# pyControl_devboard_1_2.net
KiCad netlist of a schematic drawn in EAGLE
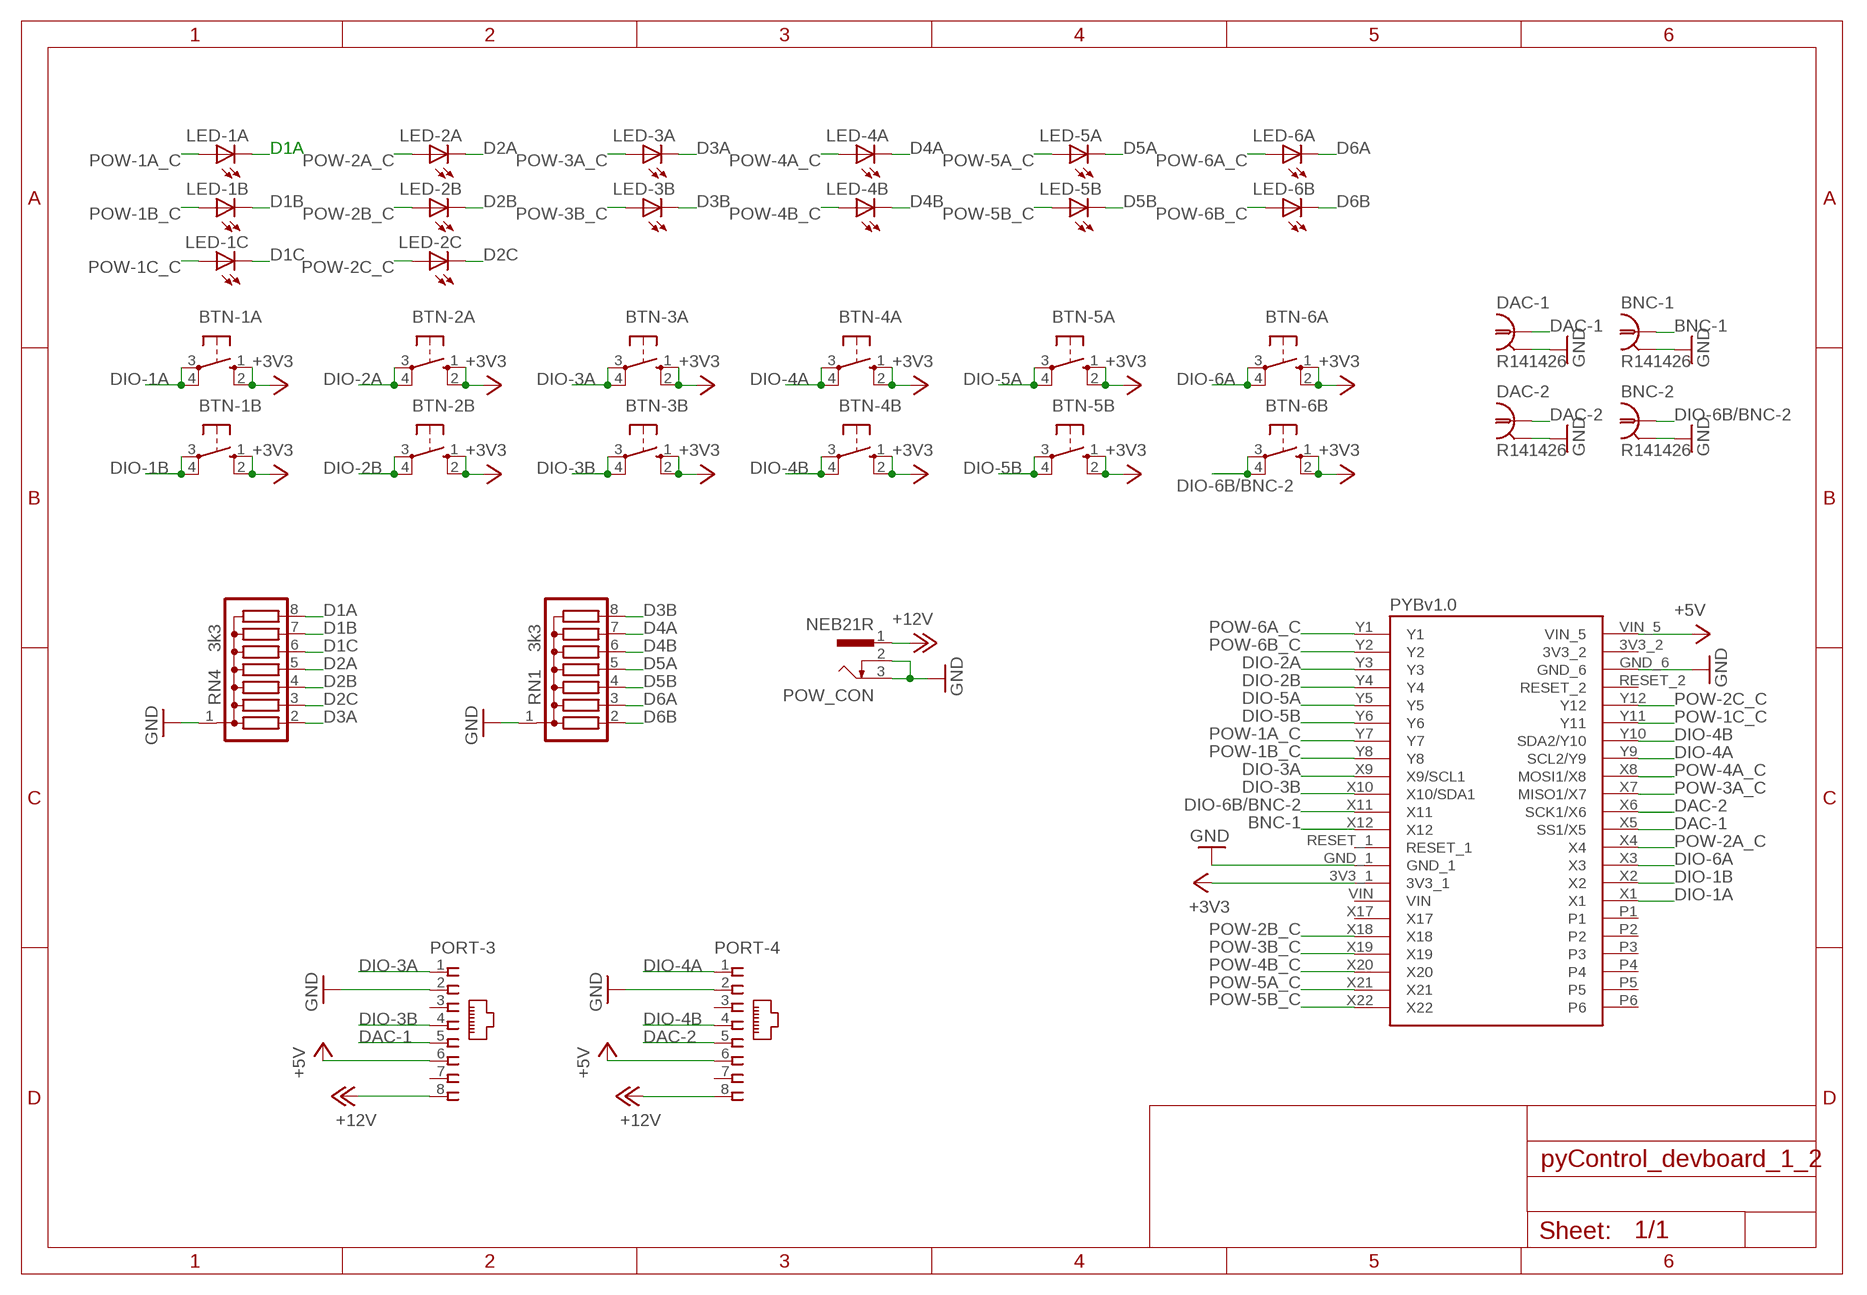
[diagram p0: schematic, sheet 1]

(export (version "E")
  (design (tool "Eeschema 10.0.6"))
  (components
    (comp (ref "BNC-1")
      (value "R141426")
      (footprint "eagle-import:R141426")
      (fields (field (name "MF") "FARNELL") (field (name "MPN") "R141426161"))
      (libsource (lib "eagle-import") (part "R141426"))
    )
    (comp (ref "BNC-2")
      (value "R141426")
      (footprint "eagle-import:R141426")
      (fields (field (name "MF") "FARNELL") (field (name "MPN") "R141426161"))
      (libsource (lib "eagle-import") (part "R141426"))
    )
    (comp (ref "BTN-1A")
      (value "40-XX")
      (footprint "eagle-import:B3F-40XX")
      (fields
        (field (name "MF") "OMRON COMPONENTS USA")
        (field (name "MPN") "B3F-4000")
        (field (name "MF_1") "OMRON COMPONENTS USA")
        (field (name "MPN_1") "B3F-4000")
        (field (name "OC_FARNELL") "176434")
        (field (name "OC_NEWARK") "36K3105")
      )
      (libsource (lib "eagle-import") (part "40-XX"))
    )
    (comp (ref "BTN-1B")
      (value "40-XX")
      (footprint "eagle-import:B3F-40XX")
      (fields
        (field (name "MF") "OMRON COMPONENTS USA")
        (field (name "MPN") "B3F-4000")
        (field (name "MF_1") "OMRON COMPONENTS USA")
        (field (name "MPN_1") "B3F-4000")
        (field (name "OC_FARNELL") "176434")
        (field (name "OC_NEWARK") "36K3105")
      )
      (libsource (lib "eagle-import") (part "40-XX"))
    )
    (comp (ref "BTN-2A")
      (value "40-XX")
      (footprint "eagle-import:B3F-40XX")
      (fields
        (field (name "MF") "OMRON COMPONENTS USA")
        (field (name "MPN") "B3F-4000")
        (field (name "MF_1") "OMRON COMPONENTS USA")
        (field (name "MPN_1") "B3F-4000")
        (field (name "OC_FARNELL") "176434")
        (field (name "OC_NEWARK") "36K3105")
      )
      (libsource (lib "eagle-import") (part "40-XX"))
    )
    (comp (ref "BTN-2B")
      (value "40-XX")
      (footprint "eagle-import:B3F-40XX")
      (fields
        (field (name "MF") "OMRON COMPONENTS USA")
        (field (name "MPN") "B3F-4000")
        (field (name "MF_1") "OMRON COMPONENTS USA")
        (field (name "MPN_1") "B3F-4000")
        (field (name "OC_FARNELL") "176434")
        (field (name "OC_NEWARK") "36K3105")
      )
      (libsource (lib "eagle-import") (part "40-XX"))
    )
    (comp (ref "BTN-3A")
      (value "40-XX")
      (footprint "eagle-import:B3F-40XX")
      (fields
        (field (name "MF") "OMRON COMPONENTS USA")
        (field (name "MPN") "B3F-4000")
        (field (name "MF_1") "OMRON COMPONENTS USA")
        (field (name "MPN_1") "B3F-4000")
        (field (name "OC_FARNELL") "176434")
        (field (name "OC_NEWARK") "36K3105")
      )
      (libsource (lib "eagle-import") (part "40-XX"))
    )
    (comp (ref "BTN-3B")
      (value "40-XX")
      (footprint "eagle-import:B3F-40XX")
      (fields
        (field (name "MF") "OMRON COMPONENTS USA")
        (field (name "MPN") "B3F-4000")
        (field (name "MF_1") "OMRON COMPONENTS USA")
        (field (name "MPN_1") "B3F-4000")
        (field (name "OC_FARNELL") "176434")
        (field (name "OC_NEWARK") "36K3105")
      )
      (libsource (lib "eagle-import") (part "40-XX"))
    )
    (comp (ref "BTN-4A")
      (value "40-XX")
      (footprint "eagle-import:B3F-40XX")
      (fields
        (field (name "MF") "OMRON COMPONENTS USA")
        (field (name "MPN") "B3F-4000")
        (field (name "MF_1") "OMRON COMPONENTS USA")
        (field (name "MPN_1") "B3F-4000")
        (field (name "OC_FARNELL") "176434")
        (field (name "OC_NEWARK") "36K3105")
      )
      (libsource (lib "eagle-import") (part "40-XX"))
    )
    (comp (ref "BTN-4B")
      (value "40-XX")
      (footprint "eagle-import:B3F-40XX")
      (fields
        (field (name "MF") "OMRON COMPONENTS USA")
        (field (name "MPN") "B3F-4000")
        (field (name "MF_1") "OMRON COMPONENTS USA")
        (field (name "MPN_1") "B3F-4000")
        (field (name "OC_FARNELL") "176434")
        (field (name "OC_NEWARK") "36K3105")
      )
      (libsource (lib "eagle-import") (part "40-XX"))
    )
    (comp (ref "BTN-5A")
      (value "40-XX")
      (footprint "eagle-import:B3F-40XX")
      (fields
        (field (name "MF") "OMRON COMPONENTS USA")
        (field (name "MPN") "B3F-4000")
        (field (name "MF_1") "OMRON COMPONENTS USA")
        (field (name "MPN_1") "B3F-4000")
        (field (name "OC_FARNELL") "176434")
        (field (name "OC_NEWARK") "36K3105")
      )
      (libsource (lib "eagle-import") (part "40-XX"))
    )
    (comp (ref "BTN-5B")
      (value "40-XX")
      (footprint "eagle-import:B3F-40XX")
      (fields
        (field (name "MF") "OMRON COMPONENTS USA")
        (field (name "MPN") "B3F-4000")
        (field (name "MF_1") "OMRON COMPONENTS USA")
        (field (name "MPN_1") "B3F-4000")
        (field (name "OC_FARNELL") "176434")
        (field (name "OC_NEWARK") "36K3105")
      )
      (libsource (lib "eagle-import") (part "40-XX"))
    )
    (comp (ref "BTN-6A")
      (value "40-XX")
      (footprint "eagle-import:B3F-40XX")
      (fields
        (field (name "MF") "OMRON COMPONENTS USA")
        (field (name "MPN") "B3F-4000")
        (field (name "MF_1") "OMRON COMPONENTS USA")
        (field (name "MPN_1") "B3F-4000")
        (field (name "OC_FARNELL") "176434")
        (field (name "OC_NEWARK") "36K3105")
      )
      (libsource (lib "eagle-import") (part "40-XX"))
    )
    (comp (ref "BTN-6B")
      (value "40-XX")
      (footprint "eagle-import:B3F-40XX")
      (fields
        (field (name "MF") "OMRON COMPONENTS USA")
        (field (name "MPN") "B3F-4000")
        (field (name "MF_1") "OMRON COMPONENTS USA")
        (field (name "MPN_1") "B3F-4000")
        (field (name "OC_FARNELL") "176434")
        (field (name "OC_NEWARK") "36K3105")
      )
      (libsource (lib "eagle-import") (part "40-XX"))
    )
    (comp (ref "DAC-1")
      (value "R141426")
      (footprint "eagle-import:R141426")
      (fields (field (name "MF") "FARNELL") (field (name "MPN") "R141426161"))
      (libsource (lib "eagle-import") (part "R141426"))
    )
    (comp (ref "DAC-2")
      (value "R141426")
      (footprint "eagle-import:R141426")
      (fields (field (name "MF") "FARNELL") (field (name "MPN") "R141426161"))
      (libsource (lib "eagle-import") (part "R141426"))
    )
    (comp (ref "LED-1A")
      (value "LED3MM")
      (footprint "eagle-import:LED3MM")
      (libsource (lib "eagle-import") (part "LED3MM"))
    )
    (comp (ref "LED-1B")
      (value "LED3MM")
      (footprint "eagle-import:LED3MM")
      (libsource (lib "eagle-import") (part "LED3MM"))
    )
    (comp (ref "LED-1C")
      (value "LED3MM")
      (footprint "eagle-import:LED3MM")
      (libsource (lib "eagle-import") (part "LED3MM"))
    )
    (comp (ref "LED-2A")
      (value "LED3MM")
      (footprint "eagle-import:LED3MM")
      (libsource (lib "eagle-import") (part "LED3MM"))
    )
    (comp (ref "LED-2B")
      (value "LED3MM")
      (footprint "eagle-import:LED3MM")
      (libsource (lib "eagle-import") (part "LED3MM"))
    )
    (comp (ref "LED-2C")
      (value "LED3MM")
      (footprint "eagle-import:LED3MM")
      (libsource (lib "eagle-import") (part "LED3MM"))
    )
    (comp (ref "LED-3A")
      (value "LED3MM")
      (footprint "eagle-import:LED3MM")
      (libsource (lib "eagle-import") (part "LED3MM"))
    )
    (comp (ref "LED-3B")
      (value "LED3MM")
      (footprint "eagle-import:LED3MM")
      (libsource (lib "eagle-import") (part "LED3MM"))
    )
    (comp (ref "LED-4A")
      (value "LED3MM")
      (footprint "eagle-import:LED3MM")
      (libsource (lib "eagle-import") (part "LED3MM"))
    )
    (comp (ref "LED-4B")
      (value "LED3MM")
      (footprint "eagle-import:LED3MM")
      (libsource (lib "eagle-import") (part "LED3MM"))
    )
    (comp (ref "LED-5A")
      (value "LED3MM")
      (footprint "eagle-import:LED3MM")
      (libsource (lib "eagle-import") (part "LED3MM"))
    )
    (comp (ref "LED-5B")
      (value "LED3MM")
      (footprint "eagle-import:LED3MM")
      (libsource (lib "eagle-import") (part "LED3MM"))
    )
    (comp (ref "LED-6A")
      (value "LED3MM")
      (footprint "eagle-import:LED3MM")
      (libsource (lib "eagle-import") (part "LED3MM"))
    )
    (comp (ref "LED-6B")
      (value "LED3MM")
      (footprint "eagle-import:LED3MM")
      (libsource (lib "eagle-import") (part "LED3MM"))
    )
    (comp (ref "PORT-3")
      (value "RJ45VERTICAL")
      (footprint "eagle-import:RJ45-NO-SHIELD-VERTICAL")
      (libsource (lib "eagle-import") (part "RJ45VERTICAL"))
    )
    (comp (ref "PORT-4")
      (value "RJ45VERTICAL")
      (footprint "eagle-import:RJ45-NO-SHIELD-VERTICAL")
      (libsource (lib "eagle-import") (part "RJ45VERTICAL"))
    )
    (comp (ref "POW_CON")
      (value "NEB21R")
      (footprint "eagle-import:NEB21R")
      (fields (field (name "MPN") "NEB 21 R"))
      (libsource (lib "eagle-import") (part "NEB21R"))
    )
    (comp (ref "PYBOARD")
      (value "PYBOARD-REDUCED-2")
      (footprint "eagle-import:PYBOARD-REDUCED-2")
      (libsource (lib "eagle-import") (part "PYBOARD-REDUCED-2"))
    )
    (comp (ref "RN1")
      (value "3k3")
      (footprint "eagle-import:SIL8")
      (libsource (lib "eagle-import") (part "G07R"))
    )
    (comp (ref "RN4")
      (value "3k3")
      (footprint "eagle-import:SIL8")
      (libsource (lib "eagle-import") (part "G07R"))
    )
  )
  (nets
    (net (code "1") (name "+3V3") (class "Default")
      (node (ref "BTN-1A") (pin "1") (pinfunction "S_1") (pintype "passive"))
      (node (ref "BTN-1A") (pin "2") (pinfunction "S1_2") (pintype "passive"))
      (node (ref "BTN-1B") (pin "1") (pinfunction "S_1") (pintype "passive"))
      (node (ref "BTN-1B") (pin "2") (pinfunction "S1_2") (pintype "passive"))
      (node (ref "BTN-2A") (pin "1") (pinfunction "S_1") (pintype "passive"))
      (node (ref "BTN-2A") (pin "2") (pinfunction "S1_2") (pintype "passive"))
      (node (ref "BTN-2B") (pin "1") (pinfunction "S_1") (pintype "passive"))
      (node (ref "BTN-2B") (pin "2") (pinfunction "S1_2") (pintype "passive"))
      (node (ref "BTN-3A") (pin "1") (pinfunction "S_1") (pintype "passive"))
      (node (ref "BTN-3A") (pin "2") (pinfunction "S1_2") (pintype "passive"))
      (node (ref "BTN-3B") (pin "1") (pinfunction "S_1") (pintype "passive"))
      (node (ref "BTN-3B") (pin "2") (pinfunction "S1_2") (pintype "passive"))
      (node (ref "BTN-4A") (pin "1") (pinfunction "S_1") (pintype "passive"))
      (node (ref "BTN-4A") (pin "2") (pinfunction "S1_2") (pintype "passive"))
      (node (ref "BTN-4B") (pin "1") (pinfunction "S_1") (pintype "passive"))
      (node (ref "BTN-4B") (pin "2") (pinfunction "S1_2") (pintype "passive"))
      (node (ref "BTN-5A") (pin "1") (pinfunction "S_1") (pintype "passive"))
      (node (ref "BTN-5A") (pin "2") (pinfunction "S1_2") (pintype "passive"))
      (node (ref "BTN-5B") (pin "1") (pinfunction "S_1") (pintype "passive"))
      (node (ref "BTN-5B") (pin "2") (pinfunction "S1_2") (pintype "passive"))
      (node (ref "BTN-6A") (pin "1") (pinfunction "S_1") (pintype "passive"))
      (node (ref "BTN-6A") (pin "2") (pinfunction "S1_2") (pintype "passive"))
      (node (ref "BTN-6B") (pin "1") (pinfunction "S_1") (pintype "passive"))
      (node (ref "BTN-6B") (pin "2") (pinfunction "S1_2") (pintype "passive"))
      (node (ref "PYBOARD") (pin "3V3_1") (pinfunction "3V3_1_3V3_1") (pintype "bidirectional"))
    )
    (net (code "2") (name "+5V") (class "Default")
      (node (ref "PORT-3") (pin "6") (pinfunction "6_6") (pintype "passive"))
      (node (ref "PORT-4") (pin "6") (pinfunction "6_6") (pintype "passive"))
      (node (ref "PYBOARD") (pin "VIN_5") (pinfunction "VIN_5_VIN_5") (pintype "bidirectional"))
    )
    (net (code "3") (name "+12V") (class "Default")
      (node (ref "PORT-3") (pin "8") (pinfunction "8_8") (pintype "passive"))
      (node (ref "PORT-4") (pin "8") (pinfunction "8_8") (pintype "passive"))
      (node (ref "POW_CON") (pin "1") (pinfunction "1_1") (pintype "passive"))
    )
    (net (code "4") (name "/BNC-1") (class "Default")
      (node (ref "BNC-1") (pin "1") (pinfunction "1_1") (pintype "passive"))
      (node (ref "PYBOARD") (pin "X12") (pinfunction "X12_X12") (pintype "bidirectional"))
    )
    (net (code "5") (name "/D1A") (class "Default")
      (node (ref "LED-1A") (pin "K") (pinfunction "C_K") (pintype "passive"))
      (node (ref "RN4") (pin "8") (pinfunction "8_8") (pintype "passive"))
    )
    (net (code "6") (name "/D1B") (class "Default")
      (node (ref "LED-1B") (pin "K") (pinfunction "C_K") (pintype "passive"))
      (node (ref "RN4") (pin "7") (pinfunction "7_7") (pintype "passive"))
    )
    (net (code "7") (name "/D1C") (class "Default")
      (node (ref "LED-1C") (pin "K") (pinfunction "C_K") (pintype "passive"))
      (node (ref "RN4") (pin "6") (pinfunction "6_6") (pintype "passive"))
    )
    (net (code "8") (name "/D2A") (class "Default")
      (node (ref "LED-2A") (pin "K") (pinfunction "C_K") (pintype "passive"))
      (node (ref "RN4") (pin "5") (pinfunction "5_5") (pintype "passive"))
    )
    (net (code "9") (name "/D2B") (class "Default")
      (node (ref "LED-2B") (pin "K") (pinfunction "C_K") (pintype "passive"))
      (node (ref "RN4") (pin "4") (pinfunction "4_4") (pintype "passive"))
    )
    (net (code "10") (name "/D2C") (class "Default")
      (node (ref "LED-2C") (pin "K") (pinfunction "C_K") (pintype "passive"))
      (node (ref "RN4") (pin "3") (pinfunction "3_3") (pintype "passive"))
    )
    (net (code "11") (name "/D3A") (class "Default")
      (node (ref "LED-3A") (pin "K") (pinfunction "C_K") (pintype "passive"))
      (node (ref "RN4") (pin "2") (pinfunction "2_2") (pintype "passive"))
    )
    (net (code "12") (name "/D3B") (class "Default")
      (node (ref "LED-3B") (pin "K") (pinfunction "C_K") (pintype "passive"))
      (node (ref "RN1") (pin "8") (pinfunction "8_8") (pintype "passive"))
    )
    (net (code "13") (name "/D4A") (class "Default")
      (node (ref "LED-4A") (pin "K") (pinfunction "C_K") (pintype "passive"))
      (node (ref "RN1") (pin "7") (pinfunction "7_7") (pintype "passive"))
    )
    (net (code "14") (name "/D4B") (class "Default")
      (node (ref "LED-4B") (pin "K") (pinfunction "C_K") (pintype "passive"))
      (node (ref "RN1") (pin "6") (pinfunction "6_6") (pintype "passive"))
    )
    (net (code "15") (name "/D5A") (class "Default")
      (node (ref "LED-5A") (pin "K") (pinfunction "C_K") (pintype "passive"))
      (node (ref "RN1") (pin "5") (pinfunction "5_5") (pintype "passive"))
    )
    (net (code "16") (name "/D5B") (class "Default")
      (node (ref "LED-5B") (pin "K") (pinfunction "C_K") (pintype "passive"))
      (node (ref "RN1") (pin "4") (pinfunction "4_4") (pintype "passive"))
    )
    (net (code "17") (name "/D6A") (class "Default")
      (node (ref "LED-6A") (pin "K") (pinfunction "C_K") (pintype "passive"))
      (node (ref "RN1") (pin "3") (pinfunction "3_3") (pintype "passive"))
    )
    (net (code "18") (name "/D6B") (class "Default")
      (node (ref "LED-6B") (pin "K") (pinfunction "C_K") (pintype "passive"))
      (node (ref "RN1") (pin "2") (pinfunction "2_2") (pintype "passive"))
    )
    (net (code "19") (name "/DAC-1") (class "Default")
      (node (ref "DAC-1") (pin "1") (pinfunction "1_1") (pintype "passive"))
      (node (ref "PORT-3") (pin "5") (pinfunction "5_5") (pintype "passive"))
      (node (ref "PYBOARD") (pin "X5") (pinfunction "SS1/X5_X5") (pintype "bidirectional"))
    )
    (net (code "20") (name "/DAC-2") (class "Default")
      (node (ref "DAC-2") (pin "1") (pinfunction "1_1") (pintype "passive"))
      (node (ref "PORT-4") (pin "5") (pinfunction "5_5") (pintype "passive"))
      (node (ref "PYBOARD") (pin "X6") (pinfunction "SCK1/X6_X6") (pintype "bidirectional"))
    )
    (net (code "21") (name "/DIO-1A") (class "Default")
      (node (ref "BTN-1A") (pin "3") (pinfunction "P_3") (pintype "passive"))
      (node (ref "BTN-1A") (pin "4") (pinfunction "P1_4") (pintype "passive"))
      (node (ref "PYBOARD") (pin "X1") (pinfunction "X1_X1") (pintype "bidirectional"))
    )
    (net (code "22") (name "/DIO-1B") (class "Default")
      (node (ref "BTN-1B") (pin "3") (pinfunction "P_3") (pintype "passive"))
      (node (ref "BTN-1B") (pin "4") (pinfunction "P1_4") (pintype "passive"))
      (node (ref "PYBOARD") (pin "X2") (pinfunction "X2_X2") (pintype "bidirectional"))
    )
    (net (code "23") (name "/DIO-2A") (class "Default")
      (node (ref "BTN-2A") (pin "3") (pinfunction "P_3") (pintype "passive"))
      (node (ref "BTN-2A") (pin "4") (pinfunction "P1_4") (pintype "passive"))
      (node (ref "PYBOARD") (pin "Y3") (pinfunction "Y3_Y3") (pintype "bidirectional"))
    )
    (net (code "24") (name "/DIO-2B") (class "Default")
      (node (ref "BTN-2B") (pin "3") (pinfunction "P_3") (pintype "passive"))
      (node (ref "BTN-2B") (pin "4") (pinfunction "P1_4") (pintype "passive"))
      (node (ref "PYBOARD") (pin "Y4") (pinfunction "Y4_Y4") (pintype "bidirectional"))
    )
    (net (code "25") (name "/DIO-3A") (class "Default")
      (node (ref "BTN-3A") (pin "3") (pinfunction "P_3") (pintype "passive"))
      (node (ref "BTN-3A") (pin "4") (pinfunction "P1_4") (pintype "passive"))
      (node (ref "PORT-3") (pin "1") (pinfunction "1_1") (pintype "passive"))
      (node (ref "PYBOARD") (pin "X9") (pinfunction "X9/SCL1_X9") (pintype "bidirectional"))
    )
    (net (code "26") (name "/DIO-3B") (class "Default")
      (node (ref "BTN-3B") (pin "3") (pinfunction "P_3") (pintype "passive"))
      (node (ref "BTN-3B") (pin "4") (pinfunction "P1_4") (pintype "passive"))
      (node (ref "PORT-3") (pin "4") (pinfunction "4_4") (pintype "passive"))
      (node (ref "PYBOARD") (pin "X10") (pinfunction "X10/SDA1_X10") (pintype "bidirectional"))
    )
    (net (code "27") (name "/DIO-4A") (class "Default")
      (node (ref "BTN-4A") (pin "3") (pinfunction "P_3") (pintype "passive"))
      (node (ref "BTN-4A") (pin "4") (pinfunction "P1_4") (pintype "passive"))
      (node (ref "PORT-4") (pin "1") (pinfunction "1_1") (pintype "passive"))
      (node (ref "PYBOARD") (pin "Y9") (pinfunction "SCL2/Y9_Y9") (pintype "bidirectional"))
    )
    (net (code "28") (name "/DIO-4B") (class "Default")
      (node (ref "BTN-4B") (pin "3") (pinfunction "P_3") (pintype "passive"))
      (node (ref "BTN-4B") (pin "4") (pinfunction "P1_4") (pintype "passive"))
      (node (ref "PORT-4") (pin "4") (pinfunction "4_4") (pintype "passive"))
      (node (ref "PYBOARD") (pin "Y10") (pinfunction "SDA2/Y10_Y10") (pintype "bidirectional"))
    )
    (net (code "29") (name "/DIO-5A") (class "Default")
      (node (ref "BTN-5A") (pin "3") (pinfunction "P_3") (pintype "passive"))
      (node (ref "BTN-5A") (pin "4") (pinfunction "P1_4") (pintype "passive"))
      (node (ref "PYBOARD") (pin "Y5") (pinfunction "Y5_Y5") (pintype "bidirectional"))
    )
    (net (code "30") (name "/DIO-5B") (class "Default")
      (node (ref "BTN-5B") (pin "3") (pinfunction "P_3") (pintype "passive"))
      (node (ref "BTN-5B") (pin "4") (pinfunction "P1_4") (pintype "passive"))
      (node (ref "PYBOARD") (pin "Y6") (pinfunction "Y6_Y6") (pintype "bidirectional"))
    )
    (net (code "31") (name "/DIO-6A") (class "Default")
      (node (ref "BTN-6A") (pin "3") (pinfunction "P_3") (pintype "passive"))
      (node (ref "BTN-6A") (pin "4") (pinfunction "P1_4") (pintype "passive"))
      (node (ref "PYBOARD") (pin "X3") (pinfunction "X3_X3") (pintype "bidirectional"))
    )
    (net (code "32") (name "/DIO-6B{slash}BNC-2") (class "Default")
      (node (ref "BNC-2") (pin "1") (pinfunction "1_1") (pintype "passive"))
      (node (ref "BTN-6B") (pin "3") (pinfunction "P_3") (pintype "passive"))
      (node (ref "BTN-6B") (pin "4") (pinfunction "P1_4") (pintype "passive"))
      (node (ref "PYBOARD") (pin "X11") (pinfunction "X11_X11") (pintype "bidirectional"))
    )
    (net (code "33") (name "/POW-1A_C") (class "Default")
      (node (ref "LED-1A") (pin "A") (pinfunction "A_A") (pintype "passive"))
      (node (ref "PYBOARD") (pin "Y7") (pinfunction "Y7_Y7") (pintype "bidirectional"))
    )
    (net (code "34") (name "/POW-1B_C") (class "Default")
      (node (ref "LED-1B") (pin "A") (pinfunction "A_A") (pintype "passive"))
      (node (ref "PYBOARD") (pin "Y8") (pinfunction "Y8_Y8") (pintype "bidirectional"))
    )
    (net (code "35") (name "/POW-1C_C") (class "Default")
      (node (ref "LED-1C") (pin "A") (pinfunction "A_A") (pintype "passive"))
      (node (ref "PYBOARD") (pin "Y11") (pinfunction "Y11_Y11") (pintype "bidirectional"))
    )
    (net (code "36") (name "/POW-2A_C") (class "Default")
      (node (ref "LED-2A") (pin "A") (pinfunction "A_A") (pintype "passive"))
      (node (ref "PYBOARD") (pin "X4") (pinfunction "X4_X4") (pintype "bidirectional"))
    )
    (net (code "37") (name "/POW-2B_C") (class "Default")
      (node (ref "LED-2B") (pin "A") (pinfunction "A_A") (pintype "passive"))
      (node (ref "PYBOARD") (pin "X18") (pinfunction "X18_X18") (pintype "bidirectional"))
    )
    (net (code "38") (name "/POW-2C_C") (class "Default")
      (node (ref "LED-2C") (pin "A") (pinfunction "A_A") (pintype "passive"))
      (node (ref "PYBOARD") (pin "Y12") (pinfunction "Y12_Y12") (pintype "bidirectional"))
    )
    (net (code "39") (name "/POW-3A_C") (class "Default")
      (node (ref "LED-3A") (pin "A") (pinfunction "A_A") (pintype "passive"))
      (node (ref "PYBOARD") (pin "X7") (pinfunction "MISO1/X7_X7") (pintype "bidirectional"))
    )
    (net (code "40") (name "/POW-3B_C") (class "Default")
      (node (ref "LED-3B") (pin "A") (pinfunction "A_A") (pintype "passive"))
      (node (ref "PYBOARD") (pin "X19") (pinfunction "X19_X19") (pintype "bidirectional"))
    )
    (net (code "41") (name "/POW-4A_C") (class "Default")
      (node (ref "LED-4A") (pin "A") (pinfunction "A_A") (pintype "passive"))
      (node (ref "PYBOARD") (pin "X8") (pinfunction "MOSI1/X8_X8") (pintype "bidirectional"))
    )
    (net (code "42") (name "/POW-4B_C") (class "Default")
      (node (ref "LED-4B") (pin "A") (pinfunction "A_A") (pintype "passive"))
      (node (ref "PYBOARD") (pin "X20") (pinfunction "X20_X20") (pintype "bidirectional"))
    )
    (net (code "43") (name "/POW-5A_C") (class "Default")
      (node (ref "LED-5A") (pin "A") (pinfunction "A_A") (pintype "passive"))
      (node (ref "PYBOARD") (pin "X21") (pinfunction "X21_X21") (pintype "bidirectional"))
    )
    (net (code "44") (name "/POW-5B_C") (class "Default")
      (node (ref "LED-5B") (pin "A") (pinfunction "A_A") (pintype "passive"))
      (node (ref "PYBOARD") (pin "X22") (pinfunction "X22_X22") (pintype "bidirectional"))
    )
    (net (code "45") (name "/POW-6A_C") (class "Default")
      (node (ref "LED-6A") (pin "A") (pinfunction "A_A") (pintype "passive"))
      (node (ref "PYBOARD") (pin "Y1") (pinfunction "Y1_Y1") (pintype "bidirectional"))
    )
    (net (code "46") (name "/POW-6B_C") (class "Default")
      (node (ref "LED-6B") (pin "A") (pinfunction "A_A") (pintype "passive"))
      (node (ref "PYBOARD") (pin "Y2") (pinfunction "Y2_Y2") (pintype "bidirectional"))
    )
    (net (code "47") (name "GND") (class "Default")
      (node (ref "BNC-1") (pin "2") (pinfunction "GND_2") (pintype "power_in"))
      (node (ref "BNC-2") (pin "2") (pinfunction "GND_2") (pintype "power_in"))
      (node (ref "DAC-1") (pin "2") (pinfunction "GND_2") (pintype "power_in"))
      (node (ref "DAC-2") (pin "2") (pinfunction "GND_2") (pintype "power_in"))
      (node (ref "PORT-3") (pin "2") (pinfunction "2_2") (pintype "passive"))
      (node (ref "PORT-4") (pin "2") (pinfunction "2_2") (pintype "passive"))
      (node (ref "POW_CON") (pin "2") (pinfunction "2_2") (pintype "passive"))
      (node (ref "POW_CON") (pin "3") (pinfunction "3_3") (pintype "passive"))
      (node (ref "PYBOARD") (pin "GND_1") (pinfunction "GND_1_GND_1") (pintype "bidirectional"))
      (node (ref "PYBOARD") (pin "GND_6") (pinfunction "GND_6_GND_6") (pintype "bidirectional"))
      (node (ref "RN1") (pin "1") (pinfunction "1_1") (pintype "passive"))
      (node (ref "RN4") (pin "1") (pinfunction "1_1") (pintype "passive"))
    )
    (net (code "48") (name "unconnected-(PORT-3-Pad3)") (class "Default")
      (node (ref "PORT-3") (pin "3") (pinfunction "3_3") (pintype "passive"))
    )
    (net (code "49") (name "unconnected-(PORT-3-Pad7)") (class "Default")
      (node (ref "PORT-3") (pin "7") (pinfunction "7_7") (pintype "passive"))
    )
    (net (code "50") (name "unconnected-(PORT-4-Pad3)") (class "Default")
      (node (ref "PORT-4") (pin "3") (pinfunction "3_3") (pintype "passive"))
    )
    (net (code "51") (name "unconnected-(PORT-4-Pad7)") (class "Default")
      (node (ref "PORT-4") (pin "7") (pinfunction "7_7") (pintype "passive"))
    )
    (net (code "52") (name "unconnected-(PYBOARD-Pad3V3_2)") (class "Default")
      (node (ref "PYBOARD") (pin "3V3_2") (pinfunction "3V3_2_3V3_2") (pintype "bidirectional"))
    )
    (net (code "53") (name "unconnected-(PYBOARD-PadP1)") (class "Default")
      (node (ref "PYBOARD") (pin "P1") (pinfunction "P1_P1") (pintype "bidirectional"))
    )
    (net (code "54") (name "unconnected-(PYBOARD-PadP2)") (class "Default")
      (node (ref "PYBOARD") (pin "P2") (pinfunction "P2_P2") (pintype "bidirectional"))
    )
    (net (code "55") (name "unconnected-(PYBOARD-PadP3)") (class "Default")
      (node (ref "PYBOARD") (pin "P3") (pinfunction "P3_P3") (pintype "bidirectional"))
    )
    (net (code "56") (name "unconnected-(PYBOARD-PadP4)") (class "Default")
      (node (ref "PYBOARD") (pin "P4") (pinfunction "P4_P4") (pintype "bidirectional"))
    )
    (net (code "57") (name "unconnected-(PYBOARD-PadP5)") (class "Default")
      (node (ref "PYBOARD") (pin "P5") (pinfunction "P5_P5") (pintype "bidirectional"))
    )
    (net (code "58") (name "unconnected-(PYBOARD-PadP6)") (class "Default")
      (node (ref "PYBOARD") (pin "P6") (pinfunction "P6_P6") (pintype "bidirectional"))
    )
    (net (code "59") (name "unconnected-(PYBOARD-PadRESET_1)") (class "Default")
      (node (ref "PYBOARD") (pin "RESET_1") (pinfunction "RESET_1_RESET_1") (pintype "bidirectional"))
    )
    (net (code "60") (name "unconnected-(PYBOARD-PadRESET_2)") (class "Default")
      (node (ref "PYBOARD") (pin "RESET_2") (pinfunction "RESET_2_RESET_2") (pintype "bidirectional"))
    )
    (net (code "61") (name "unconnected-(PYBOARD-PadVIN)") (class "Default")
      (node (ref "PYBOARD") (pin "VIN") (pinfunction "VIN_VIN") (pintype "bidirectional"))
    )
    (net (code "62") (name "unconnected-(PYBOARD-PadX17)") (class "Default")
      (node (ref "PYBOARD") (pin "X17") (pinfunction "X17_X17") (pintype "bidirectional"))
    )
  )
)
